# Baxandall.net
KiCad netlist of a schematic drawn in Altium Designer
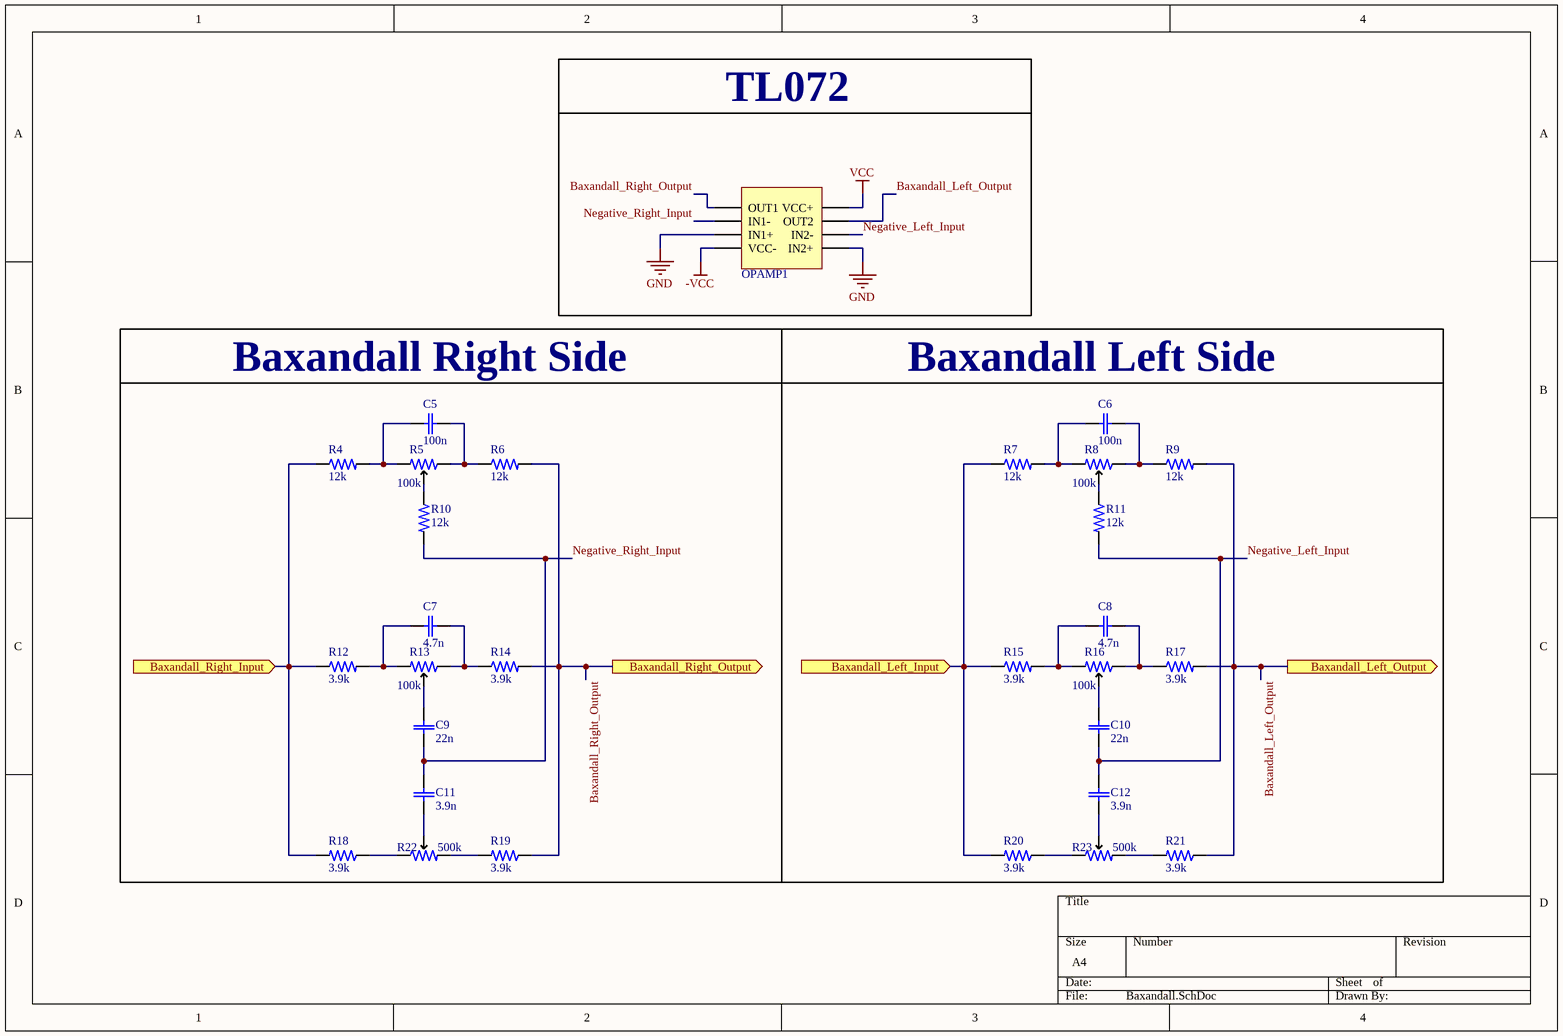
[diagram p0: Baxandall.SchDoc]

(export (version "E")
  (design (tool "Eeschema 10.0.6"))
  (components
    (comp (ref "C5")
      (value "100n")
      (footprint "CERAMIC0603")
      (fields (field (name "MF") "KEMET") (field (name "MP") "TAJC226M025RNJ"))
      (libsource (lib "AltiumLibrary-Mugetsu") (part "Cap"))
    )
    (comp (ref "C6")
      (value "100n")
      (footprint "CERAMIC0603")
      (fields (field (name "MF") "KEMET") (field (name "MP") "TAJC226M025RNJ"))
      (libsource (lib "AltiumLibrary-Mugetsu") (part "Cap"))
    )
    (comp (ref "C7")
      (value "4.7n")
      (footprint "CERAMIC0603")
      (fields (field (name "MF") "KEMET") (field (name "MP") "TAJC226M025RNJ"))
      (libsource (lib "AltiumLibrary-Mugetsu") (part "Cap"))
    )
    (comp (ref "C8")
      (value "4.7n")
      (footprint "CERAMIC0603")
      (fields (field (name "MF") "KEMET") (field (name "MP") "TAJC226M025RNJ"))
      (libsource (lib "AltiumLibrary-Mugetsu") (part "Cap"))
    )
    (comp (ref "C9")
      (value "22n")
      (footprint "CERAMIC0603")
      (fields (field (name "MF") "KEMET") (field (name "MP") "TAJC226M025RNJ"))
      (libsource (lib "AltiumLibrary-Mugetsu") (part "Cap"))
    )
    (comp (ref "C10")
      (value "22n")
      (footprint "CERAMIC0603")
      (fields (field (name "MF") "KEMET") (field (name "MP") "TAJC226M025RNJ"))
      (libsource (lib "AltiumLibrary-Mugetsu") (part "Cap"))
    )
    (comp (ref "C11")
      (value "3.9n")
      (footprint "CERAMIC0603")
      (fields (field (name "MF") "KEMET") (field (name "MP") "TAJC226M025RNJ"))
      (libsource (lib "AltiumLibrary-Mugetsu") (part "Cap"))
    )
    (comp (ref "C12")
      (value "3.9n")
      (footprint "CERAMIC0603")
      (fields (field (name "MF") "KEMET") (field (name "MP") "TAJC226M025RNJ"))
      (libsource (lib "AltiumLibrary-Mugetsu") (part "Cap"))
    )
    (comp (ref "OPAMP1")
      (value "TL072")
      (footprint "DIP8")
      (libsource (lib "AltiumLibrary-Mugetsu") (part "TL072"))
    )
    (comp (ref "R4")
      (value "12k")
      (footprint "RES0603")
      (fields (field (name "MP") "3-1879460-6"))
      (libsource (lib "AltiumLibrary-Mugetsu") (part "RESISTOR SMD"))
    )
    (comp (ref "R5")
      (value "100k")
      (footprint "Potentiometer THT")
      (libsource (lib "AltiumLibrary-Mugetsu") (part "Potentiometer"))
    )
    (comp (ref "R6")
      (value "12k")
      (footprint "RES0603")
      (fields (field (name "MP") "3-1879460-6"))
      (libsource (lib "AltiumLibrary-Mugetsu") (part "RESISTOR SMD"))
    )
    (comp (ref "R7")
      (value "12k")
      (footprint "RES0603")
      (fields (field (name "MP") "3-1879460-6"))
      (libsource (lib "AltiumLibrary-Mugetsu") (part "RESISTOR SMD"))
    )
    (comp (ref "R8")
      (value "100k")
      (footprint "Potentiometer THT")
      (libsource (lib "AltiumLibrary-Mugetsu") (part "Potentiometer"))
    )
    (comp (ref "R9")
      (value "12k")
      (footprint "RES0603")
      (fields (field (name "MP") "3-1879460-6"))
      (libsource (lib "AltiumLibrary-Mugetsu") (part "RESISTOR SMD"))
    )
    (comp (ref "R10")
      (value "12k")
      (footprint "RES0603")
      (fields (field (name "MP") "3-1879460-6"))
      (libsource (lib "AltiumLibrary-Mugetsu") (part "RESISTOR SMD"))
    )
    (comp (ref "R11")
      (value "12k")
      (footprint "RES0603")
      (fields (field (name "MP") "3-1879460-6"))
      (libsource (lib "AltiumLibrary-Mugetsu") (part "RESISTOR SMD"))
    )
    (comp (ref "R12")
      (value "3.9k")
      (footprint "RES0603")
      (fields (field (name "MP") "3-1879460-6"))
      (libsource (lib "AltiumLibrary-Mugetsu") (part "RESISTOR SMD"))
    )
    (comp (ref "R13")
      (value "100k")
      (footprint "Potentiometer THT")
      (libsource (lib "AltiumLibrary-Mugetsu") (part "Potentiometer"))
    )
    (comp (ref "R14")
      (value "3.9k")
      (footprint "RES0603")
      (fields (field (name "MP") "3-1879460-6"))
      (libsource (lib "AltiumLibrary-Mugetsu") (part "RESISTOR SMD"))
    )
    (comp (ref "R15")
      (value "3.9k")
      (footprint "RES0603")
      (fields (field (name "MP") "3-1879460-6"))
      (libsource (lib "AltiumLibrary-Mugetsu") (part "RESISTOR SMD"))
    )
    (comp (ref "R16")
      (value "100k")
      (footprint "Potentiometer THT")
      (libsource (lib "AltiumLibrary-Mugetsu") (part "Potentiometer"))
    )
    (comp (ref "R17")
      (value "3.9k")
      (footprint "RES0603")
      (fields (field (name "MP") "3-1879460-6"))
      (libsource (lib "AltiumLibrary-Mugetsu") (part "RESISTOR SMD"))
    )
    (comp (ref "R18")
      (value "3.9k")
      (footprint "RES0603")
      (fields (field (name "MP") "3-1879460-6"))
      (libsource (lib "AltiumLibrary-Mugetsu") (part "RESISTOR SMD"))
    )
    (comp (ref "R19")
      (value "3.9k")
      (footprint "RES0603")
      (fields (field (name "MP") "3-1879460-6"))
      (libsource (lib "AltiumLibrary-Mugetsu") (part "RESISTOR SMD"))
    )
    (comp (ref "R20")
      (value "3.9k")
      (footprint "RES0603")
      (fields (field (name "MP") "3-1879460-6"))
      (libsource (lib "AltiumLibrary-Mugetsu") (part "RESISTOR SMD"))
    )
    (comp (ref "R21")
      (value "3.9k")
      (footprint "RES0603")
      (fields (field (name "MP") "3-1879460-6"))
      (libsource (lib "AltiumLibrary-Mugetsu") (part "RESISTOR SMD"))
    )
    (comp (ref "R22")
      (value "500k")
      (footprint "Potentiometer THT")
      (libsource (lib "AltiumLibrary-Mugetsu") (part "Potentiometer"))
    )
    (comp (ref "R23")
      (value "500k")
      (footprint "Potentiometer THT")
      (libsource (lib "AltiumLibrary-Mugetsu") (part "Potentiometer"))
    )
  )
  (nets
    (net (code "1") (name "-VCC") (class "Default")
      (node (ref "OPAMP1") (pin "4") (pinfunction "VCC-_4") (pintype "passive"))
    )
    (net (code "2") (name "/Baxandall_Left_Input") (class "Default")
      (node (ref "R15") (pin "1") (pinfunction "1_1") (pintype "passive"))
      (node (ref "R20") (pin "2") (pinfunction "2_2") (pintype "passive"))
      (node (ref "R7") (pin "1") (pinfunction "1_1") (pintype "passive"))
    )
    (net (code "3") (name "/Baxandall_Left_Output") (class "Default")
      (node (ref "OPAMP1") (pin "7") (pinfunction "OUT2_7") (pintype "passive"))
      (node (ref "R17") (pin "2") (pinfunction "2_2") (pintype "passive"))
      (node (ref "R21") (pin "1") (pinfunction "1_1") (pintype "passive"))
      (node (ref "R9") (pin "2") (pinfunction "2_2") (pintype "passive"))
    )
    (net (code "4") (name "/Baxandall_Right_Input") (class "Default")
      (node (ref "R12") (pin "1") (pinfunction "1_1") (pintype "passive"))
      (node (ref "R18") (pin "2") (pinfunction "2_2") (pintype "passive"))
      (node (ref "R4") (pin "1") (pinfunction "1_1") (pintype "passive"))
    )
    (net (code "5") (name "/Baxandall_Right_Output") (class "Default")
      (node (ref "OPAMP1") (pin "1") (pinfunction "OUT1_1") (pintype "passive"))
      (node (ref "R14") (pin "2") (pinfunction "2_2") (pintype "passive"))
      (node (ref "R19") (pin "1") (pinfunction "1_1") (pintype "passive"))
      (node (ref "R6") (pin "2") (pinfunction "2_2") (pintype "passive"))
    )
    (net (code "6") (name "/Negative_Left_Input") (class "Default")
      (node (ref "C10") (pin "1") (pinfunction "C1_1") (pintype "passive"))
      (node (ref "C12") (pin "1") (pinfunction "C1_1") (pintype "passive"))
      (node (ref "OPAMP1") (pin "6") (pinfunction "IN2-_6") (pintype "passive"))
      (node (ref "R11") (pin "2") (pinfunction "2_2") (pintype "passive"))
    )
    (net (code "7") (name "/Negative_Right_Input") (class "Default")
      (node (ref "C11") (pin "1") (pinfunction "C1_1") (pintype "passive"))
      (node (ref "C9") (pin "1") (pinfunction "C1_1") (pintype "passive"))
      (node (ref "OPAMP1") (pin "2") (pinfunction "IN1-_2") (pintype "passive"))
      (node (ref "R10") (pin "2") (pinfunction "2_2") (pintype "passive"))
    )
    (net (code "8") (name "GND") (class "Default")
      (node (ref "OPAMP1") (pin "3") (pinfunction "IN1+_3") (pintype "passive"))
      (node (ref "OPAMP1") (pin "5") (pinfunction "IN2+_5") (pintype "passive"))
    )
    (net (code "9") (name "Net-(C5-C1)") (class "Default")
      (node (ref "C5") (pin "1") (pinfunction "C1_1") (pintype "passive"))
      (node (ref "R4") (pin "2") (pinfunction "2_2") (pintype "passive"))
      (node (ref "R5") (pin "2") (pinfunction "2_2") (pintype "passive"))
    )
    (net (code "10") (name "Net-(C5-C2)") (class "Default")
      (node (ref "C5") (pin "2") (pinfunction "C2_2") (pintype "passive"))
      (node (ref "R5") (pin "1") (pinfunction "1_1") (pintype "passive"))
      (node (ref "R6") (pin "1") (pinfunction "1_1") (pintype "passive"))
    )
    (net (code "11") (name "Net-(C6-C1)") (class "Default")
      (node (ref "C6") (pin "1") (pinfunction "C1_1") (pintype "passive"))
      (node (ref "R7") (pin "2") (pinfunction "2_2") (pintype "passive"))
      (node (ref "R8") (pin "2") (pinfunction "2_2") (pintype "passive"))
    )
    (net (code "12") (name "Net-(C6-C2)") (class "Default")
      (node (ref "C6") (pin "2") (pinfunction "C2_2") (pintype "passive"))
      (node (ref "R8") (pin "1") (pinfunction "1_1") (pintype "passive"))
      (node (ref "R9") (pin "1") (pinfunction "1_1") (pintype "passive"))
    )
    (net (code "13") (name "Net-(C7-C1)") (class "Default")
      (node (ref "C7") (pin "1") (pinfunction "C1_1") (pintype "passive"))
      (node (ref "R12") (pin "2") (pinfunction "2_2") (pintype "passive"))
      (node (ref "R13") (pin "2") (pinfunction "2_2") (pintype "passive"))
    )
    (net (code "14") (name "Net-(C7-C2)") (class "Default")
      (node (ref "C7") (pin "2") (pinfunction "C2_2") (pintype "passive"))
      (node (ref "R13") (pin "1") (pinfunction "1_1") (pintype "passive"))
      (node (ref "R14") (pin "1") (pinfunction "1_1") (pintype "passive"))
    )
    (net (code "15") (name "Net-(C8-C1)") (class "Default")
      (node (ref "C8") (pin "1") (pinfunction "C1_1") (pintype "passive"))
      (node (ref "R15") (pin "2") (pinfunction "2_2") (pintype "passive"))
      (node (ref "R16") (pin "2") (pinfunction "2_2") (pintype "passive"))
    )
    (net (code "16") (name "Net-(C8-C2)") (class "Default")
      (node (ref "C8") (pin "2") (pinfunction "C2_2") (pintype "passive"))
      (node (ref "R16") (pin "1") (pinfunction "1_1") (pintype "passive"))
      (node (ref "R17") (pin "1") (pinfunction "1_1") (pintype "passive"))
    )
    (net (code "17") (name "Net-(C9-C2)") (class "Default")
      (node (ref "C9") (pin "2") (pinfunction "C2_2") (pintype "passive"))
      (node (ref "R13") (pin "3") (pinfunction "3_3") (pintype "passive"))
    )
    (net (code "18") (name "Net-(C10-C2)") (class "Default")
      (node (ref "C10") (pin "2") (pinfunction "C2_2") (pintype "passive"))
      (node (ref "R16") (pin "3") (pinfunction "3_3") (pintype "passive"))
    )
    (net (code "19") (name "Net-(C11-C2)") (class "Default")
      (node (ref "C11") (pin "2") (pinfunction "C2_2") (pintype "passive"))
      (node (ref "R22") (pin "3") (pinfunction "3_3") (pintype "passive"))
    )
    (net (code "20") (name "Net-(C12-C2)") (class "Default")
      (node (ref "C12") (pin "2") (pinfunction "C2_2") (pintype "passive"))
      (node (ref "R23") (pin "3") (pinfunction "3_3") (pintype "passive"))
    )
    (net (code "21") (name "Net-(R10-Pad1)") (class "Default")
      (node (ref "R10") (pin "1") (pinfunction "1_1") (pintype "passive"))
      (node (ref "R5") (pin "3") (pinfunction "3_3") (pintype "passive"))
    )
    (net (code "22") (name "Net-(R11-Pad1)") (class "Default")
      (node (ref "R11") (pin "1") (pinfunction "1_1") (pintype "passive"))
      (node (ref "R8") (pin "3") (pinfunction "3_3") (pintype "passive"))
    )
    (net (code "23") (name "Net-(R18-Pad1)") (class "Default")
      (node (ref "R18") (pin "1") (pinfunction "1_1") (pintype "passive"))
      (node (ref "R22") (pin "1") (pinfunction "1_1") (pintype "passive"))
    )
    (net (code "24") (name "Net-(R19-Pad2)") (class "Default")
      (node (ref "R19") (pin "2") (pinfunction "2_2") (pintype "passive"))
      (node (ref "R22") (pin "2") (pinfunction "2_2") (pintype "passive"))
    )
    (net (code "25") (name "Net-(R20-Pad1)") (class "Default")
      (node (ref "R20") (pin "1") (pinfunction "1_1") (pintype "passive"))
      (node (ref "R23") (pin "1") (pinfunction "1_1") (pintype "passive"))
    )
    (net (code "26") (name "Net-(R21-Pad2)") (class "Default")
      (node (ref "R21") (pin "2") (pinfunction "2_2") (pintype "passive"))
      (node (ref "R23") (pin "2") (pinfunction "2_2") (pintype "passive"))
    )
    (net (code "27") (name "VCC") (class "Default")
      (node (ref "OPAMP1") (pin "8") (pinfunction "VCC+_8") (pintype "passive"))
    )
  )
)
